# Morpheus.net
KiCad netlist of a schematic drawn in Altium Designer
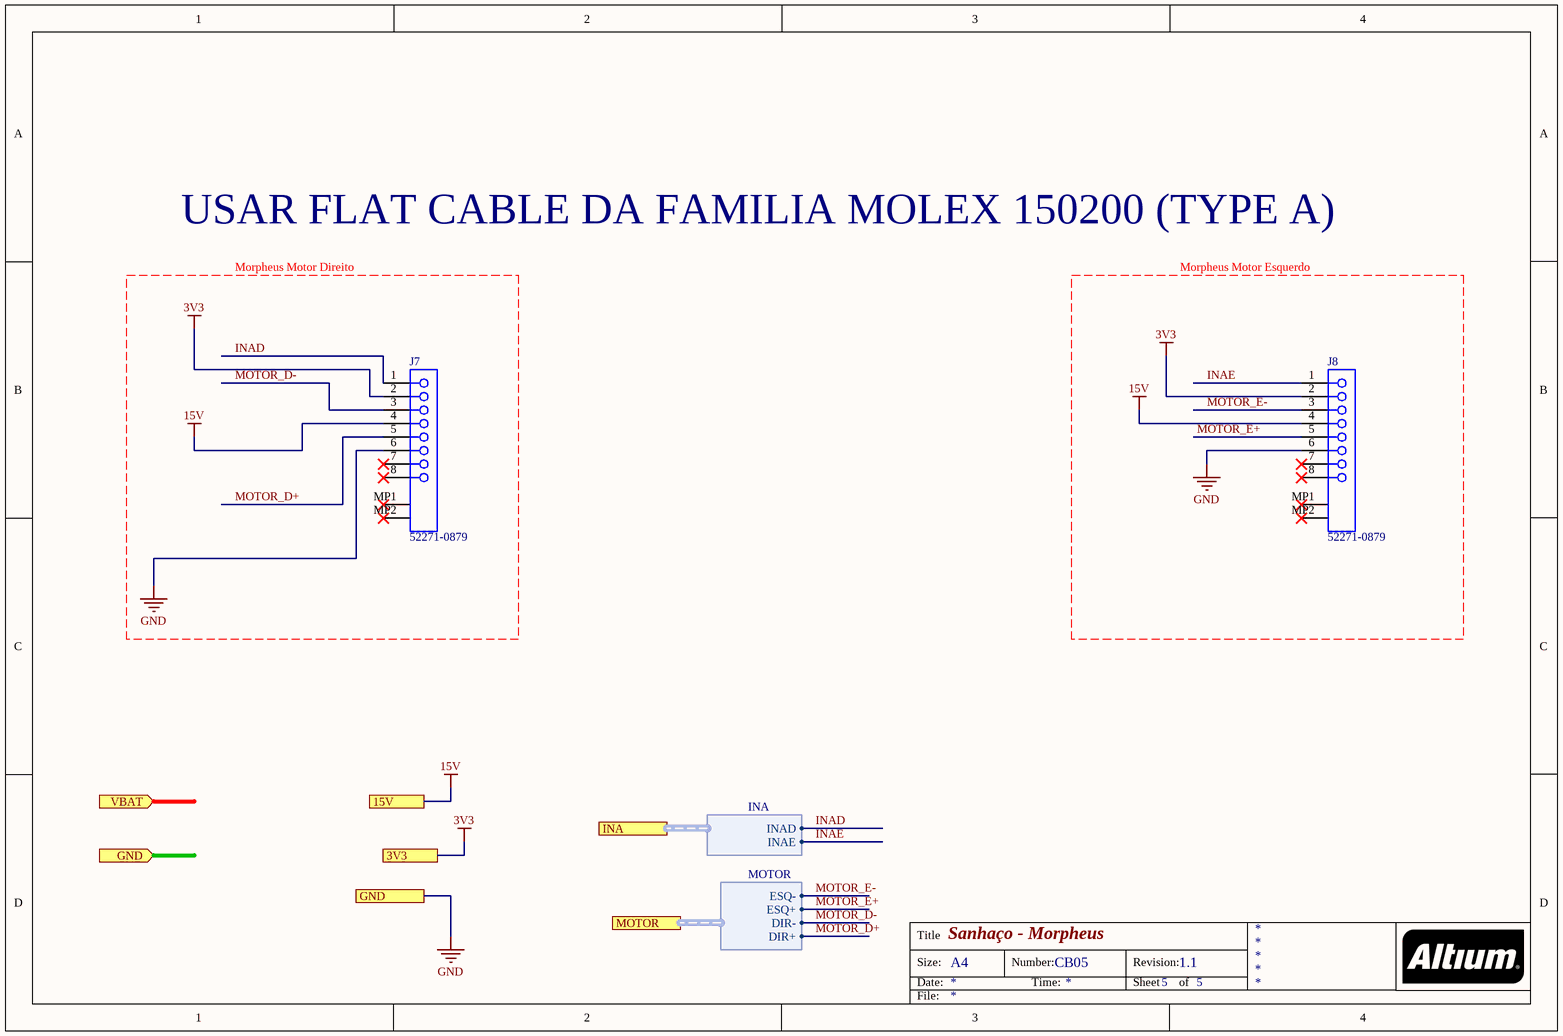
[diagram p0: Morpheus.SchDoc]

(export (version "E")
  (design (tool "Eeschema 10.0.6"))
  (components
    (comp (ref "J7")
      (value "52271-0879")
      (footprint "MOLX-52271-0879")
      (fields (field (name "MANUFACTURER") "Molex"))
      (libsource (lib "Altium Content Vault") (part "MOLX-52271-0879"))
    )
    (comp (ref "J8")
      (value "52271-0879")
      (footprint "MOLX-52271-0879")
      (fields (field (name "MANUFACTURER") "Molex"))
      (libsource (lib "Altium Content Vault") (part "MOLX-52271-0879"))
    )
  )
  (nets
    (net (code "3") (name "/INAD") (class "Default")
      (node (ref "J7") (pin "1") (pinfunction "1_1") (pintype "passive"))
    )
    (net (code "4") (name "/INAE") (class "Default")
      (node (ref "J8") (pin "1") (pinfunction "1_1") (pintype "passive"))
    )
    (net (code "5") (name "/MOTOR_D+") (class "Default")
      (node (ref "J7") (pin "5") (pinfunction "5_5") (pintype "passive"))
    )
    (net (code "6") (name "/MOTOR_D-") (class "Default")
      (node (ref "J7") (pin "3") (pinfunction "3_3") (pintype "passive"))
    )
    (net (code "7") (name "/MOTOR_E+") (class "Default")
      (node (ref "J8") (pin "5") (pinfunction "5_5") (pintype "passive"))
    )
    (net (code "8") (name "/MOTOR_E-") (class "Default")
      (node (ref "J8") (pin "3") (pinfunction "3_3") (pintype "passive"))
    )
    (net (code "12") (name "3V3") (class "Default")
      (node (ref "J7") (pin "2") (pinfunction "2_2") (pintype "passive"))
      (node (ref "J8") (pin "2") (pinfunction "2_2") (pintype "passive"))
    )
    (net (code "13") (name "15V") (class "Default")
      (node (ref "J7") (pin "4") (pinfunction "4_4") (pintype "passive"))
      (node (ref "J8") (pin "4") (pinfunction "4_4") (pintype "passive"))
    )
    (net (code "14") (name "GND") (class "Default")
      (node (ref "J7") (pin "6") (pinfunction "6_6") (pintype "passive"))
      (node (ref "J8") (pin "6") (pinfunction "6_6") (pintype "passive"))
    )
    (net (code "15") (name "unconnected-(J7-Pad7)") (class "Default")
      (node (ref "J7") (pin "7") (pinfunction "7_7") (pintype "passive+no_connect"))
    )
    (net (code "16") (name "unconnected-(J7-Pad8)") (class "Default")
      (node (ref "J7") (pin "8") (pinfunction "8_8") (pintype "passive+no_connect"))
    )
    (net (code "17") (name "unconnected-(J7-PadMP1)") (class "Default")
      (node (ref "J7") (pin "MP1") (pinfunction "MP1_MP1") (pintype "passive+no_connect"))
    )
    (net (code "18") (name "unconnected-(J7-PadMP2)") (class "Default")
      (node (ref "J7") (pin "MP2") (pinfunction "MP2_MP2") (pintype "passive+no_connect"))
    )
    (net (code "19") (name "unconnected-(J8-Pad7)") (class "Default")
      (node (ref "J8") (pin "7") (pinfunction "7_7") (pintype "passive+no_connect"))
    )
    (net (code "20") (name "unconnected-(J8-Pad8)") (class "Default")
      (node (ref "J8") (pin "8") (pinfunction "8_8") (pintype "passive+no_connect"))
    )
    (net (code "21") (name "unconnected-(J8-PadMP1)") (class "Default")
      (node (ref "J8") (pin "MP1") (pinfunction "MP1_MP1") (pintype "passive+no_connect"))
    )
    (net (code "22") (name "unconnected-(J8-PadMP2)") (class "Default")
      (node (ref "J8") (pin "MP2") (pinfunction "MP2_MP2") (pintype "passive+no_connect"))
    )
  )
)
